# 01_MAIN.net
KiCad netlist of a schematic drawn in Altium Designer
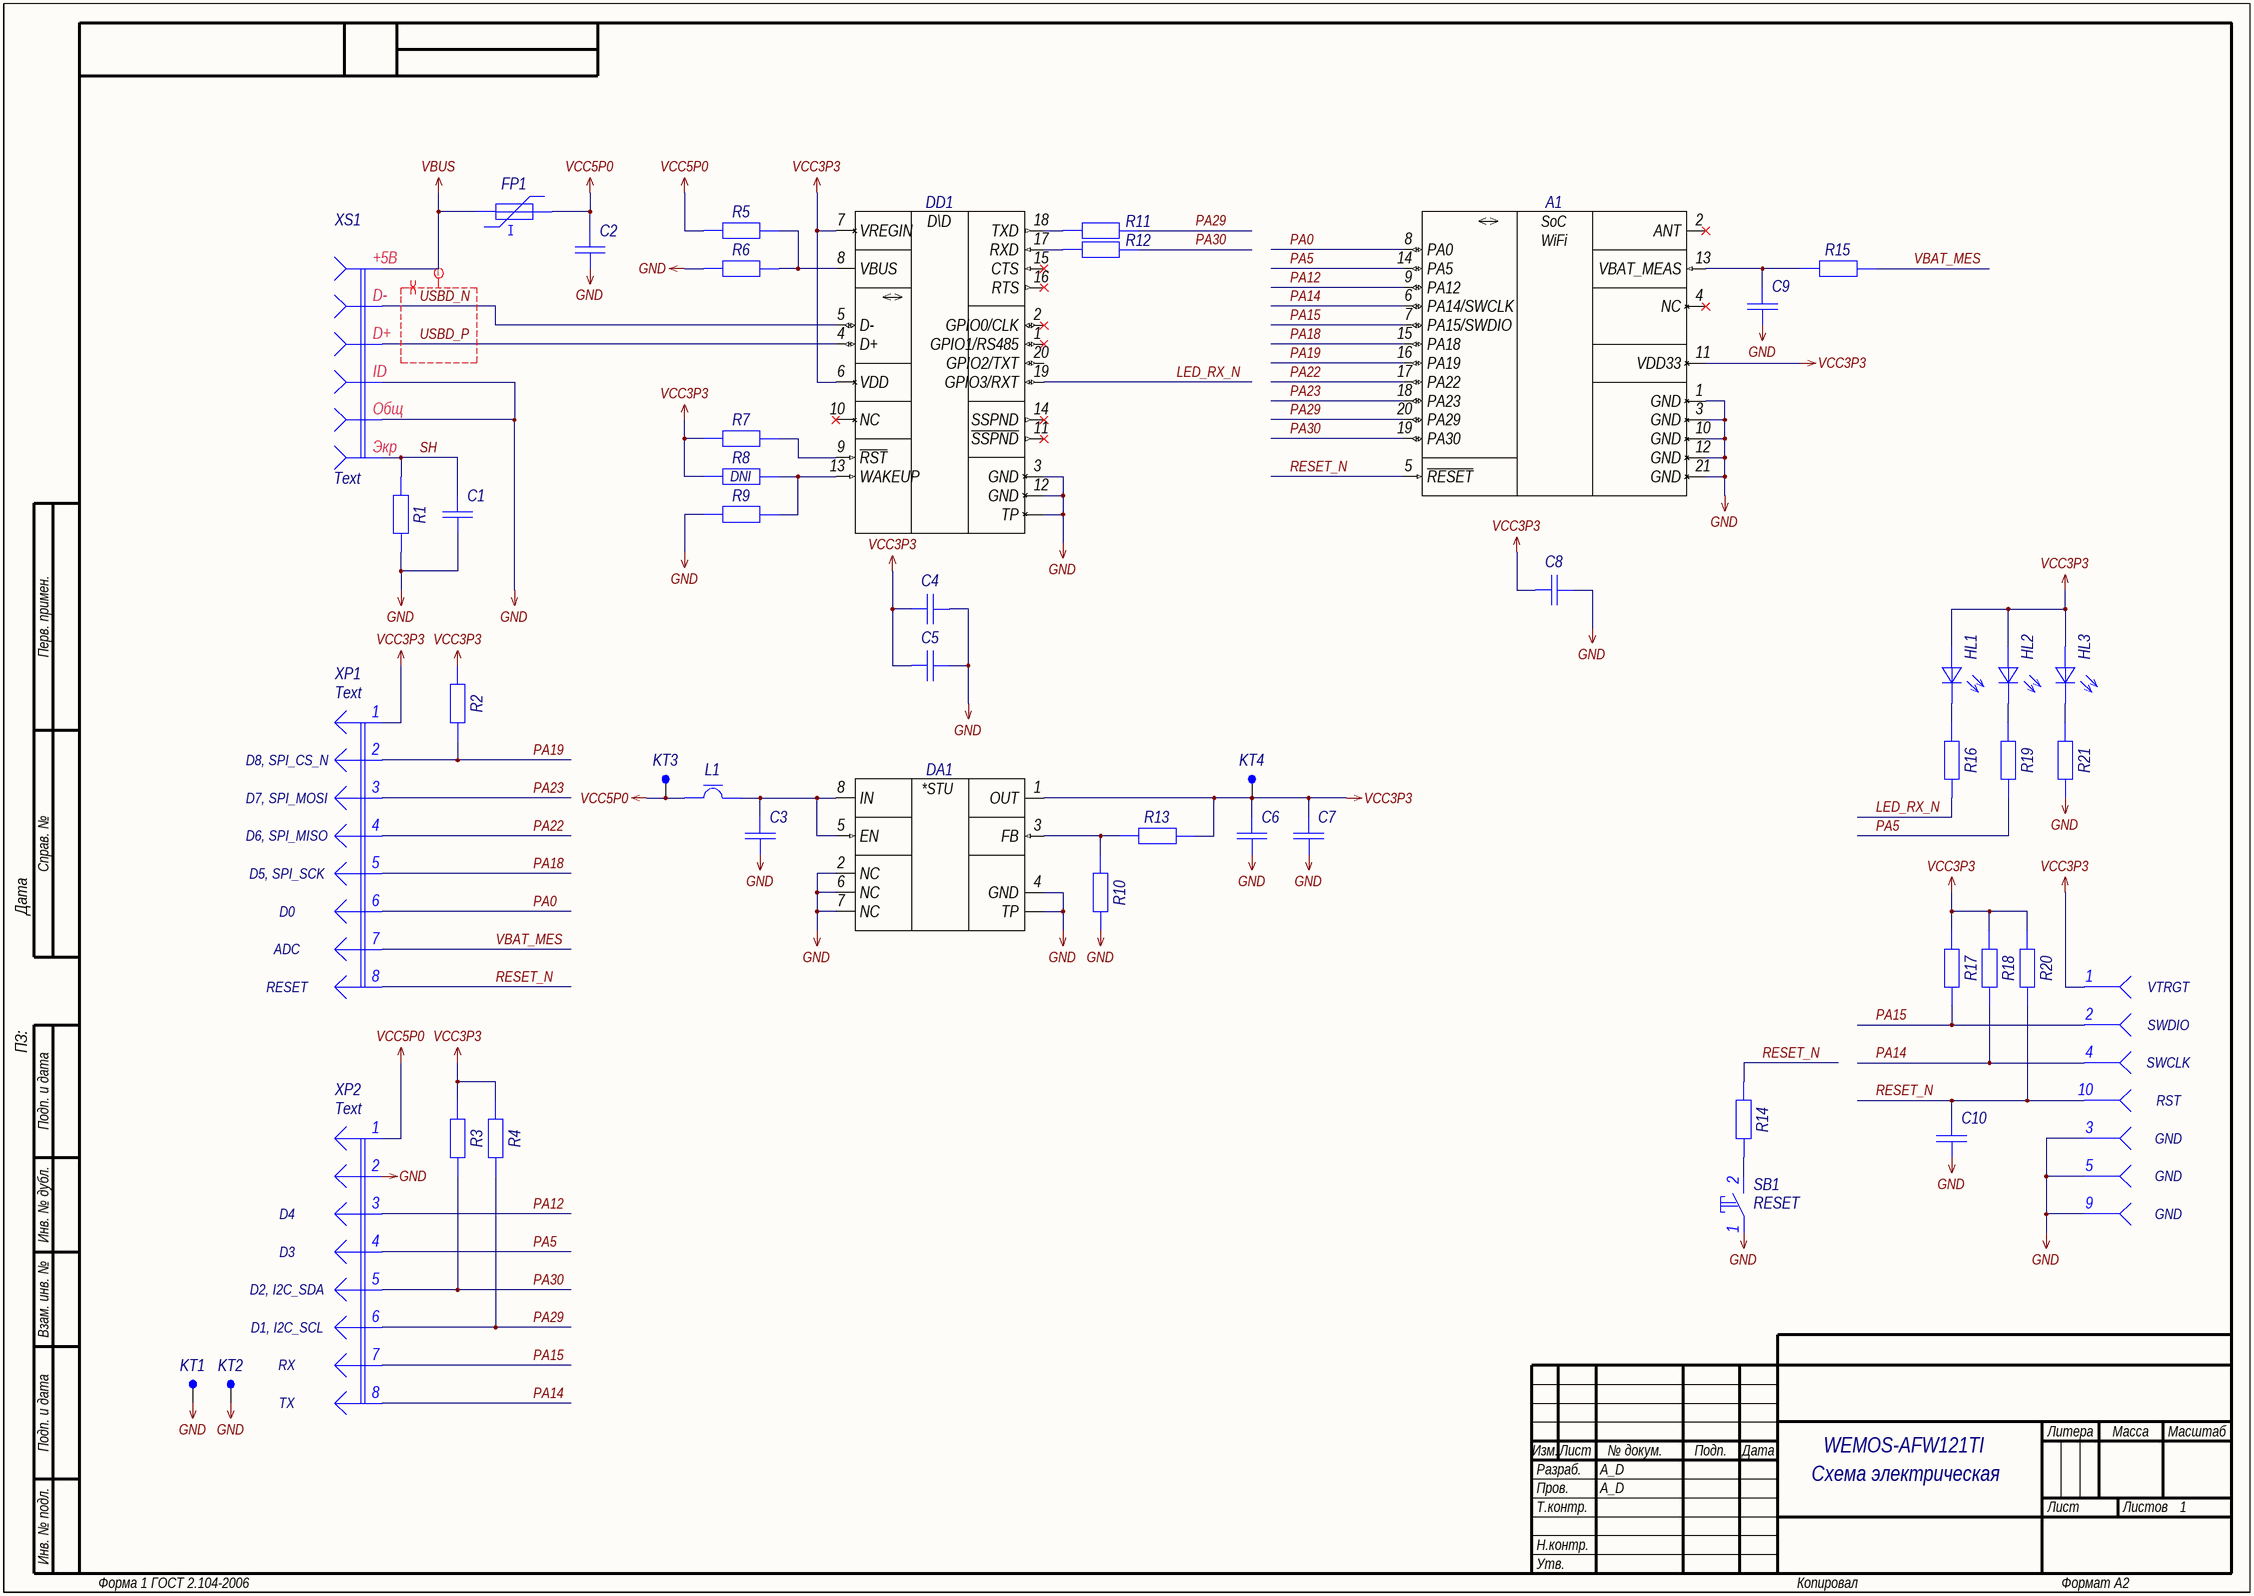
[diagram p0: 01_MAIN.SchDoc]

(export (version "E")
  (design (tool "Eeschema 10.0.6"))
  (components
    (comp (ref "A1")
      (value "AFW121TI")
      (footprint "AFW121TI")
      (fields (field (name "MANUFACTURER") "99IOT") (field (name "PUBLISHER") "Andrew Danich"))
      (libsource (lib "ADLib") (part "AFW121TI"))
    )
    (comp (ref "C1")
      (value "Capacitor")
      (footprint "C0603_L")
      (fields
        (field (name "PART NUMBER") "GRM188R72A104KA35D")
        (field (name "VOLTAGE") "100V")
        (field (name "TOLERANCE") "±10%")
        (field (name "PUBLISHER") "Andrew Danich")
      )
      (libsource (lib "ADLib") (part "Capacitor"))
    )
    (comp (ref "C2")
      (value "Capacitor")
      (footprint "C0603_L")
      (fields
        (field (name "PART NUMBER") "GRM188R60J106ME47D")
        (field (name "VOLTAGE") "6.3V")
        (field (name "TOLERANCE") "±20%")
        (field (name "PUBLISHER") "Andrew Danich")
      )
      (libsource (lib "ADLib") (part "Capacitor"))
    )
    (comp (ref "C3")
      (value "Capacitor")
      (footprint "C0402_L")
      (fields
        (field (name "PART NUMBER") "GRM155R60J475ME87D")
        (field (name "VOLTAGE") "6.3V")
        (field (name "TOLERANCE") "±20%")
        (field (name "PUBLISHER") "Andrew Danich")
      )
      (libsource (lib "ADLib") (part "Capacitor"))
    )
    (comp (ref "C4")
      (value "Capacitor")
      (footprint "C0402_L")
      (fields
        (field (name "PART NUMBER") "GRM155R60J475ME87D")
        (field (name "VOLTAGE") "6.3V")
        (field (name "TOLERANCE") "±20%")
        (field (name "PUBLISHER") "Andrew Danich")
      )
      (libsource (lib "ADLib") (part "Capacitor"))
    )
    (comp (ref "C5")
      (value "Capacitor")
      (footprint "C0402_L")
      (fields
        (field (name "PART NUMBER") "GCM155R71C104KA55D")
        (field (name "VOLTAGE") "16V")
        (field (name "TOLERANCE") "±10%")
        (field (name "PUBLISHER") "Andrew Danich")
      )
      (libsource (lib "ADLib") (part "Capacitor"))
    )
    (comp (ref "C6")
      (value "Capacitor")
      (footprint "C0402_L")
      (fields
        (field (name "PART NUMBER") "GRM155R60J475ME87D")
        (field (name "VOLTAGE") "6.3V")
        (field (name "TOLERANCE") "±20%")
        (field (name "PUBLISHER") "Andrew Danich")
      )
      (libsource (lib "ADLib") (part "Capacitor"))
    )
    (comp (ref "C7")
      (value "Capacitor")
      (footprint "C0402_L")
      (fields
        (field (name "PART NUMBER") "GRM155R60J475ME87D")
        (field (name "VOLTAGE") "6.3V")
        (field (name "TOLERANCE") "±20%")
        (field (name "PUBLISHER") "Andrew Danich")
      )
      (libsource (lib "ADLib") (part "Capacitor"))
    )
    (comp (ref "C8")
      (value "Capacitor")
      (footprint "C0402_L")
      (fields
        (field (name "PART NUMBER") "GRM155R60J475ME87D")
        (field (name "VOLTAGE") "6.3V")
        (field (name "TOLERANCE") "±20%")
        (field (name "PUBLISHER") "Andrew Danich")
      )
      (libsource (lib "ADLib") (part "Capacitor"))
    )
    (comp (ref "C9")
      (value "Capacitor")
      (footprint "C0402_L")
      (fields
        (field (name "PART NUMBER") "GCM1555C1H101FA16D")
        (field (name "VOLTAGE") "50V")
        (field (name "TOLERANCE") "±1%")
        (field (name "PUBLISHER") "Andrew Danich")
      )
      (libsource (lib "ADLib") (part "Capacitor"))
    )
    (comp (ref "C10")
      (value "Capacitor")
      (footprint "C0402_L")
      (fields
        (field (name "PART NUMBER") "GCM155R71C104KA55D")
        (field (name "VOLTAGE") "16V")
        (field (name "TOLERANCE") "±10%")
        (field (name "PUBLISHER") "Andrew Danich")
      )
      (libsource (lib "ADLib") (part "Capacitor"))
    )
    (comp (ref "DA1")
      (value "TPS73701DRB")
      (footprint "VSON-8_065P300X300X100_N")
      (fields
        (field (name "PART NUMBER") "TPS73701DRBR")
        (field (name "MANUFACTURER") "Texas Instruments")
        (field (name "PUBLISHER") "Andrew Danich")
      )
      (libsource (lib "ADLib") (part "TPS73701DRB"))
    )
    (comp (ref "DD1")
      (value "CP2102N-xxx-GQFN20")
      (footprint "QFN-20_050P300X300X080_N")
      (fields
        (field (name "PART NUMBER") "CP2102N-A01-GQFN20")
        (field (name "MANUFACTURER") "Silicon Labs")
        (field (name "PUBLISHER") "Andrew Danich")
      )
      (libsource (lib "ADLib") (part "CP2102N-xxx-GQFN20"))
    )
    (comp (ref "FP1")
      (value "Fuse_PTC")
      (footprint "F0603_L_H075")
      (fields (field (name "PART NUMBER") "0603L100SLYR") (field (name "MANUFACTURER") "Littelfuse"))
      (libsource (lib "ADLib") (part "Fuse_PTC"))
    )
    (comp (ref "HL1")
      (value "RX")
      (footprint "LD0402_L")
      (fields
        (field (name "PART NUMBER") "KPHHS-1005SURCK")
        (field (name "MANUFACTURER") "Kingbright")
        (field (name "PUBLISHER") "Andrew Danich")
      )
      (libsource (lib "ADLib") (part "Led-1"))
    )
    (comp (ref "HL2")
      (value "USER")
      (footprint "LD0402_L")
      (fields
        (field (name "PART NUMBER") "KPHHS-1005QBC-D-V")
        (field (name "MANUFACTURER") "Kingbright")
        (field (name "PUBLISHER") "Andrew Danich")
      )
      (libsource (lib "ADLib") (part "Led-1"))
    )
    (comp (ref "HL3")
      (value "POWER")
      (footprint "LD0402_L")
      (fields
        (field (name "PART NUMBER") "KPHHS-1005CGCK")
        (field (name "MANUFACTURER") "Kingbright")
        (field (name "PUBLISHER") "Andrew Danich")
      )
      (libsource (lib "ADLib") (part "Led-1"))
    )
    (comp (ref "KT1")
      (value "GND")
      (footprint "TP-SMT-R-0.8mm")
      (fields (field (name "PART NUMBER") "TestPoint-SMT-GND") (field (name "PUBLISHER") "Andrew Danich"))
      (libsource (lib "ADLib") (part "TP-S-1"))
    )
    (comp (ref "KT2")
      (value "GND")
      (footprint "TP-SMT-R-0.8mm")
      (fields (field (name "PART NUMBER") "TestPoint-SMT-GND") (field (name "PUBLISHER") "Andrew Danich"))
      (libsource (lib "ADLib") (part "TP-S-1"))
    )
    (comp (ref "KT3")
      (value "+5P0")
      (footprint "TP-SMT-C-0.5mm")
      (fields (field (name "PART NUMBER") "TestPoint-SMT") (field (name "PUBLISHER") "Andrew Danich"))
      (libsource (lib "ADLib") (part "TP-S-1"))
    )
    (comp (ref "KT4")
      (value "+3P3")
      (footprint "TP-SMT-C-0.5mm")
      (fields (field (name "PART NUMBER") "TestPoint-SMT") (field (name "PUBLISHER") "Andrew Danich"))
      (libsource (lib "ADLib") (part "TP-S-1"))
    )
    (comp (ref "L1")
      (value "FerriteBead")
      (footprint "L0402_L")
      (fields
        (field (name "PART NUMBER") "BLM15PD121SN1D")
        (field (name "TOLERANCE") "±25%")
        (field (name "MANUFACTURER") "Murata")
        (field (name "PUBLISHER") "Andrew Danich")
      )
      (libsource (lib "ADLib") (part "FerriteBead"))
    )
    (comp (ref "R1")
      (value "Resistor")
      (footprint "R0603_L")
      (fields
        (field (name "PART NUMBER") "RC0603JR-070R")
        (field (name "TOLERANCE") "±5%")
        (field (name "MANUFACTURER") "Yageo")
        (field (name "PUBLISHER") "Andrew Danich")
      )
      (libsource (lib "ADLib") (part "Resistor"))
    )
    (comp (ref "R2")
      (value "Resistor")
      (footprint "R0402_L")
      (fields
        (field (name "PART NUMBER") "RC0402JR-0710KL")
        (field (name "TOLERANCE") "±5%")
        (field (name "MANUFACTURER") "Yageo")
        (field (name "PUBLISHER") "Andrew Danich")
      )
      (libsource (lib "ADLib") (part "Resistor"))
    )
    (comp (ref "R3")
      (value "Resistor")
      (footprint "R0402_L")
      (fields
        (field (name "PART NUMBER") "RC0402JR-0710KL")
        (field (name "TOLERANCE") "±5%")
        (field (name "MANUFACTURER") "Yageo")
        (field (name "PUBLISHER") "Andrew Danich")
      )
      (libsource (lib "ADLib") (part "Resistor"))
    )
    (comp (ref "R4")
      (value "Resistor")
      (footprint "R0402_L")
      (fields
        (field (name "PART NUMBER") "RC0402JR-0710KL")
        (field (name "TOLERANCE") "±5%")
        (field (name "MANUFACTURER") "Yageo")
        (field (name "PUBLISHER") "Andrew Danich")
      )
      (libsource (lib "ADLib") (part "Resistor"))
    )
    (comp (ref "R5")
      (value "Resistor")
      (footprint "R0402_L")
      (fields
        (field (name "PART NUMBER") "RC0402FR-0722K1L")
        (field (name "TOLERANCE") "±1%")
        (field (name "MANUFACTURER") "Yageo")
        (field (name "PUBLISHER") "Andrew Danich")
      )
      (libsource (lib "ADLib") (part "Resistor"))
    )
    (comp (ref "R6")
      (value "Resistor")
      (footprint "R0402_L")
      (fields
        (field (name "PART NUMBER") "RC0402FR-0747KL")
        (field (name "TOLERANCE") "±1%")
        (field (name "MANUFACTURER") "Yageo")
        (field (name "PUBLISHER") "Andrew Danich")
      )
      (libsource (lib "ADLib") (part "Resistor"))
    )
    (comp (ref "R7")
      (value "Resistor")
      (footprint "R0402_L")
      (fields
        (field (name "PART NUMBER") "RC0402JR-0710KL")
        (field (name "TOLERANCE") "±5%")
        (field (name "MANUFACTURER") "Yageo")
        (field (name "PUBLISHER") "Andrew Danich")
      )
      (libsource (lib "ADLib") (part "Resistor"))
    )
    (comp (ref "R8")
      (value "Resistor")
      (footprint "R0402_L")
      (fields
        (field (name "PART NUMBER") "RC0402JR-0710KL")
        (field (name "TOLERANCE") "±5%")
        (field (name "MANUFACTURER") "Yageo")
        (field (name "PUBLISHER") "Andrew Danich")
      )
      (libsource (lib "ADLib") (part "Resistor"))
    )
    (comp (ref "R9")
      (value "Resistor")
      (footprint "R0402_L")
      (fields
        (field (name "PART NUMBER") "RC0402JR-070RL")
        (field (name "TOLERANCE") "±5%")
        (field (name "MANUFACTURER") "Yageo")
        (field (name "PUBLISHER") "Andrew Danich")
      )
      (libsource (lib "ADLib") (part "Resistor"))
    )
    (comp (ref "R10")
      (value "Resistor")
      (footprint "R0402_L")
      (fields
        (field (name "PART NUMBER") "RC0402FR-0712KL")
        (field (name "TOLERANCE") "±1%")
        (field (name "MANUFACTURER") "Yageo")
        (field (name "PUBLISHER") "Andrew Danich")
      )
      (libsource (lib "ADLib") (part "Resistor"))
    )
    (comp (ref "R11")
      (value "Resistor")
      (footprint "R0402_L")
      (fields
        (field (name "PART NUMBER") "RC0402JR-070RL")
        (field (name "TOLERANCE") "±5%")
        (field (name "MANUFACTURER") "Yageo")
        (field (name "PUBLISHER") "Andrew Danich")
      )
      (libsource (lib "ADLib") (part "Resistor"))
    )
    (comp (ref "R12")
      (value "Resistor")
      (footprint "R0402_L")
      (fields
        (field (name "PART NUMBER") "RC0402JR-070RL")
        (field (name "TOLERANCE") "±5%")
        (field (name "MANUFACTURER") "Yageo")
        (field (name "PUBLISHER") "Andrew Danich")
      )
      (libsource (lib "ADLib") (part "Resistor"))
    )
    (comp (ref "R13")
      (value "Resistor")
      (footprint "R0402_L")
      (fields
        (field (name "PART NUMBER") "RC0402FR-0722K1L")
        (field (name "TOLERANCE") "±1%")
        (field (name "MANUFACTURER") "Yageo")
        (field (name "PUBLISHER") "Andrew Danich")
      )
      (libsource (lib "ADLib") (part "Resistor"))
    )
    (comp (ref "R14")
      (value "Resistor")
      (footprint "R0402_L")
      (fields
        (field (name "PART NUMBER") "RC0402JR-0720RL")
        (field (name "TOLERANCE") "±5%")
        (field (name "MANUFACTURER") "Yageo")
        (field (name "PUBLISHER") "Andrew Danich")
      )
      (libsource (lib "ADLib") (part "Resistor"))
    )
    (comp (ref "R15")
      (value "Resistor")
      (footprint "R0402_L")
      (fields
        (field (name "PART NUMBER") "RC0402JR-07100RL")
        (field (name "TOLERANCE") "±5%")
        (field (name "MANUFACTURER") "Yageo")
        (field (name "PUBLISHER") "Andrew Danich")
      )
      (libsource (lib "ADLib") (part "Resistor"))
    )
    (comp (ref "R16")
      (value "Resistor")
      (footprint "R0402_L")
      (fields
        (field (name "PART NUMBER") "RC0402JR-071KL")
        (field (name "TOLERANCE") "±5%")
        (field (name "MANUFACTURER") "Yageo")
        (field (name "PUBLISHER") "Andrew Danich")
      )
      (libsource (lib "ADLib") (part "Resistor"))
    )
    (comp (ref "R17")
      (value "Resistor")
      (footprint "R0402_L")
      (fields
        (field (name "PART NUMBER") "RC0402JR-0710KL")
        (field (name "TOLERANCE") "±5%")
        (field (name "MANUFACTURER") "Yageo")
        (field (name "PUBLISHER") "Andrew Danich")
      )
      (libsource (lib "ADLib") (part "Resistor"))
    )
    (comp (ref "R18")
      (value "Resistor")
      (footprint "R0402_L")
      (fields
        (field (name "PART NUMBER") "RC0402JR-0710KL")
        (field (name "TOLERANCE") "±5%")
        (field (name "MANUFACTURER") "Yageo")
        (field (name "PUBLISHER") "Andrew Danich")
      )
      (libsource (lib "ADLib") (part "Resistor"))
    )
    (comp (ref "R19")
      (value "Resistor")
      (footprint "R0402_L")
      (fields
        (field (name "PART NUMBER") "RC0402JR-071KL")
        (field (name "TOLERANCE") "±5%")
        (field (name "MANUFACTURER") "Yageo")
        (field (name "PUBLISHER") "Andrew Danich")
      )
      (libsource (lib "ADLib") (part "Resistor"))
    )
    (comp (ref "R20")
      (value "Resistor")
      (footprint "R0402_L")
      (fields
        (field (name "PART NUMBER") "RC0402JR-0710KL")
        (field (name "TOLERANCE") "±5%")
        (field (name "MANUFACTURER") "Yageo")
        (field (name "PUBLISHER") "Andrew Danich")
      )
      (libsource (lib "ADLib") (part "Resistor"))
    )
    (comp (ref "R21")
      (value "Resistor")
      (footprint "R0402_L")
      (fields
        (field (name "PART NUMBER") "RC0402JR-071KL")
        (field (name "TOLERANCE") "±5%")
        (field (name "MANUFACTURER") "Yageo")
        (field (name "PUBLISHER") "Andrew Danich")
      )
      (libsource (lib "ADLib") (part "Resistor"))
    )
    (comp (ref "SB1")
      (value "RESET")
      (footprint "1TS003B-Series")
      (fields
        (field (name "PART NUMBER") "1TS003B-1600-3500A-CT")
        (field (name "MANUFACTURER") "Hongyuan Precision")
        (field (name "PUBLISHER") "Andrew Danich")
      )
      (libsource (lib "ADLib") (part "BT-01x-01p"))
    )
    (comp (ref "XP1")
      (value "Text")
      (footprint "PLS-8")
      (fields (field (name "PART NUMBER") "PLS-8") (field (name "PUBLISHER") "Andrew Danich"))
      (libsource (lib "ADLib") (part "Con-8-M"))
    )
    (comp (ref "XP2")
      (value "Text")
      (footprint "PLS-8")
      (fields (field (name "PART NUMBER") "PLS-8") (field (name "PUBLISHER") "Andrew Danich"))
      (libsource (lib "ADLib") (part "Con-8-M"))
    )
    (comp (ref "XS1")
      (value "Text")
      (footprint "1981568-1")
      (fields
        (field (name "PART NUMBER") "1981568-1")
        (field (name "MANUFACTURER") "TE Connectivity")
        (field (name "PUBLISHER") "Andrew Danich")
      )
      (libsource (lib "ADLib") (part "Con-6-F-USB"))
    )
    (comp (ref "XS2")
      (value "JTAG")
      (footprint "XF2M-1015-1A")
      (fields
        (field (name "PART NUMBER") "XF2M-1015-1A")
        (field (name "MANUFACTURER") "Omron Electronics")
        (field (name "PUBLISHER") "Viktor Klishin")
      )
      (libsource (lib "ADLib") (part "Con-10-F_S"))
    )
  )
  (nets
    (net (code "1") (name "/LED_RX_N") (class "Default")
      (node (ref "DD1") (pin "19") (pinfunction "GPIO3/RXT_19") (pintype "bidirectional"))
      (node (ref "R16") (pin "1") (pinfunction "1_1") (pintype "passive"))
    )
    (net (code "2") (name "/PA0") (class "Default")
      (node (ref "A1") (pin "8") (pinfunction "PA0_8") (pintype "bidirectional"))
      (node (ref "XP1") (pin "6") (pintype "passive"))
    )
    (net (code "3") (name "/PA5") (class "Default")
      (node (ref "A1") (pin "14") (pinfunction "PA5_14") (pintype "bidirectional"))
      (node (ref "R19") (pin "1") (pinfunction "1_1") (pintype "passive"))
      (node (ref "XP2") (pin "4") (pintype "passive"))
    )
    (net (code "4") (name "/PA12") (class "Default")
      (node (ref "A1") (pin "9") (pinfunction "PA12_9") (pintype "bidirectional"))
      (node (ref "XP2") (pin "3") (pintype "passive"))
    )
    (net (code "5") (name "/PA14") (class "Default")
      (node (ref "A1") (pin "6") (pinfunction "PA14/SWCLK_6") (pintype "bidirectional"))
      (node (ref "R18") (pin "2") (pinfunction "2_2") (pintype "passive"))
      (node (ref "XP2") (pin "8") (pintype "passive"))
      (node (ref "XS2") (pin "4") (pintype "passive"))
    )
    (net (code "6") (name "/PA15") (class "Default")
      (node (ref "A1") (pin "7") (pinfunction "PA15/SWDIO_7") (pintype "bidirectional"))
      (node (ref "R17") (pin "2") (pinfunction "2_2") (pintype "passive"))
      (node (ref "XP2") (pin "7") (pintype "passive"))
      (node (ref "XS2") (pin "2") (pintype "passive"))
    )
    (net (code "7") (name "/PA18") (class "Default")
      (node (ref "A1") (pin "15") (pinfunction "PA18_15") (pintype "bidirectional"))
      (node (ref "XP1") (pin "5") (pintype "passive"))
    )
    (net (code "8") (name "/PA19") (class "Default")
      (node (ref "A1") (pin "16") (pinfunction "PA19_16") (pintype "bidirectional"))
      (node (ref "R2") (pin "2") (pinfunction "2_2") (pintype "passive"))
      (node (ref "XP1") (pin "2") (pintype "passive"))
    )
    (net (code "9") (name "/PA22") (class "Default")
      (node (ref "A1") (pin "17") (pinfunction "PA22_17") (pintype "bidirectional"))
      (node (ref "XP1") (pin "4") (pintype "passive"))
    )
    (net (code "10") (name "/PA23") (class "Default")
      (node (ref "A1") (pin "18") (pinfunction "PA23_18") (pintype "bidirectional"))
      (node (ref "XP1") (pin "3") (pintype "passive"))
    )
    (net (code "11") (name "/PA29") (class "Default")
      (node (ref "A1") (pin "20") (pinfunction "PA29_20") (pintype "bidirectional"))
      (node (ref "R11") (pin "2") (pinfunction "2_2") (pintype "passive"))
      (node (ref "R4") (pin "2") (pinfunction "2_2") (pintype "passive"))
      (node (ref "XP2") (pin "6") (pintype "passive"))
    )
    (net (code "12") (name "/PA30") (class "Default")
      (node (ref "A1") (pin "19") (pinfunction "PA30_19") (pintype "bidirectional"))
      (node (ref "R12") (pin "2") (pinfunction "2_2") (pintype "passive"))
      (node (ref "R3") (pin "2") (pinfunction "2_2") (pintype "passive"))
      (node (ref "XP2") (pin "5") (pintype "passive"))
    )
    (net (code "13") (name "/RESET_N") (class "Default")
      (node (ref "A1") (pin "5") (pinfunction "~{RESET}_5") (pintype "input"))
      (node (ref "C10") (pin "2") (pinfunction "2_2") (pintype "passive"))
      (node (ref "R14") (pin "2") (pinfunction "2_2") (pintype "passive"))
      (node (ref "R20") (pin "2") (pinfunction "2_2") (pintype "passive"))
      (node (ref "XP1") (pin "8") (pintype "passive"))
      (node (ref "XS2") (pin "10") (pintype "passive"))
    )
    (net (code "14") (name "/SH") (class "Default")
      (node (ref "C1") (pin "2") (pinfunction "2_2") (pintype "passive"))
      (node (ref "R1") (pin "2") (pinfunction "2_2") (pintype "passive"))
      (node (ref "XS1") (pin "6") (pintype "passive"))
    )
    (net (code "15") (name "/USBD_N") (class "Default")
      (node (ref "DD1") (pin "5") (pinfunction "D-_5") (pintype "bidirectional"))
      (node (ref "XS1") (pin "2") (pintype "passive"))
    )
    (net (code "16") (name "/USBD_P") (class "Default")
      (node (ref "DD1") (pin "4") (pinfunction "D+_4") (pintype "bidirectional"))
      (node (ref "XS1") (pin "3") (pintype "passive"))
    )
    (net (code "17") (name "/VBAT_MES") (class "Default")
      (node (ref "R15") (pin "2") (pinfunction "2_2") (pintype "passive"))
      (node (ref "XP1") (pin "7") (pintype "passive"))
    )
    (net (code "18") (name "GND") (class "Default")
      (node (ref "A1") (pin "1") (pinfunction "GND_1") (pintype "power_in"))
      (node (ref "A1") (pin "10") (pinfunction "GND_10") (pintype "power_in"))
      (node (ref "A1") (pin "12") (pinfunction "GND_12") (pintype "power_in"))
      (node (ref "A1") (pin "21") (pinfunction "GND_21") (pintype "power_in"))
      (node (ref "A1") (pin "3") (pinfunction "GND_3") (pintype "power_in"))
      (node (ref "C1") (pin "1") (pinfunction "1_1") (pintype "passive"))
      (node (ref "C10") (pin "1") (pinfunction "1_1") (pintype "passive"))
      (node (ref "C2") (pin "1") (pinfunction "1_1") (pintype "passive"))
      (node (ref "C3") (pin "1") (pinfunction "1_1") (pintype "passive"))
      (node (ref "C4") (pin "1") (pinfunction "1_1") (pintype "passive"))
      (node (ref "C5") (pin "1") (pinfunction "1_1") (pintype "passive"))
      (node (ref "C6") (pin "1") (pinfunction "1_1") (pintype "passive"))
      (node (ref "C7") (pin "1") (pinfunction "1_1") (pintype "passive"))
      (node (ref "C8") (pin "1") (pinfunction "1_1") (pintype "passive"))
      (node (ref "C9") (pin "1") (pinfunction "1_1") (pintype "passive"))
      (node (ref "DA1") (pin "2") (pinfunction "NC_2") (pintype "passive"))
      (node (ref "DA1") (pin "4") (pinfunction "GND_4") (pintype "power_in"))
      (node (ref "DA1") (pin "6") (pinfunction "NC_6") (pintype "passive"))
      (node (ref "DA1") (pin "7") (pinfunction "NC_7") (pintype "passive"))
      (node (ref "DA1") (pin "TP") (pinfunction "TP_TP") (pintype "passive"))
      (node (ref "DD1") (pin "12") (pinfunction "GND_12") (pintype "power_in"))
      (node (ref "DD1") (pin "3") (pinfunction "GND_3") (pintype "power_in"))
      (node (ref "DD1") (pin "TP") (pinfunction "TP_TP") (pintype "power_in"))
      (node (ref "KT1") (pin "1") (pinfunction "1_1") (pintype "passive"))
      (node (ref "KT2") (pin "1") (pinfunction "1_1") (pintype "passive"))
      (node (ref "R1") (pin "1") (pinfunction "1_1") (pintype "passive"))
      (node (ref "R10") (pin "1") (pinfunction "1_1") (pintype "passive"))
      (node (ref "R21") (pin "1") (pinfunction "1_1") (pintype "passive"))
      (node (ref "R6") (pin "1") (pinfunction "1_1") (pintype "passive"))
      (node (ref "R9") (pin "1") (pinfunction "1_1") (pintype "passive"))
      (node (ref "SB1") (pin "1") (pintype "passive"))
      (node (ref "XP2") (pin "2") (pintype "passive"))
      (node (ref "XS1") (pin "4") (pintype "passive"))
      (node (ref "XS1") (pin "5") (pintype "passive"))
      (node (ref "XS2") (pin "3") (pintype "passive"))
      (node (ref "XS2") (pin "5") (pintype "passive"))
      (node (ref "XS2") (pin "9") (pintype "passive"))
    )
    (net (code "19") (name "Net-(A1-VBAT_MEAS)") (class "Default")
      (node (ref "A1") (pin "13") (pinfunction "VBAT_MEAS_13") (pintype "input"))
      (node (ref "C9") (pin "2") (pinfunction "2_2") (pintype "passive"))
      (node (ref "R15") (pin "1") (pinfunction "1_1") (pintype "passive"))
    )
    (net (code "20") (name "Net-(DA1-EN)") (class "Default")
      (node (ref "C3") (pin "2") (pinfunction "2_2") (pintype "passive"))
      (node (ref "DA1") (pin "5") (pinfunction "EN_5") (pintype "input"))
      (node (ref "DA1") (pin "8") (pinfunction "IN_8") (pintype "power_in"))
      (node (ref "L1") (pin "2") (pinfunction "2_2") (pintype "passive"))
    )
    (net (code "21") (name "Net-(DA1-FB)") (class "Default")
      (node (ref "DA1") (pin "3") (pinfunction "FB_3") (pintype "input"))
      (node (ref "R10") (pin "2") (pinfunction "2_2") (pintype "passive"))
      (node (ref "R13") (pin "1") (pinfunction "1_1") (pintype "passive"))
    )
    (net (code "22") (name "Net-(DD1-RXD)") (class "Default")
      (node (ref "DD1") (pin "17") (pinfunction "RXD_17") (pintype "input"))
      (node (ref "R12") (pin "1") (pinfunction "1_1") (pintype "passive"))
    )
    (net (code "23") (name "Net-(DD1-TXD)") (class "Default")
      (node (ref "DD1") (pin "18") (pinfunction "TXD_18") (pintype "output"))
      (node (ref "R11") (pin "1") (pinfunction "1_1") (pintype "passive"))
    )
    (net (code "24") (name "Net-(DD1-VBUS)") (class "Default")
      (node (ref "DD1") (pin "8") (pinfunction "VBUS_8") (pintype "power_in"))
      (node (ref "R5") (pin "2") (pinfunction "2_2") (pintype "passive"))
      (node (ref "R6") (pin "2") (pinfunction "2_2") (pintype "passive"))
    )
    (net (code "25") (name "Net-(DD1-WAKEUP)") (class "Default")
      (node (ref "DD1") (pin "13") (pinfunction "WAKEUP_13") (pintype "input"))
      (node (ref "R8") (pin "1") (pinfunction "1_1") (pintype "passive"))
      (node (ref "R9") (pin "2") (pinfunction "2_2") (pintype "passive"))
    )
    (net (code "26") (name "Net-(DD1-~{RST})") (class "Default")
      (node (ref "DD1") (pin "9") (pinfunction "~{RST}_9") (pintype "input"))
      (node (ref "R7") (pin "1") (pinfunction "1_1") (pintype "passive"))
    )
    (net (code "27") (name "Net-(HL1-К)") (class "Default")
      (node (ref "HL1") (pin "2") (pinfunction "К_2") (pintype "passive"))
      (node (ref "R16") (pin "2") (pinfunction "2_2") (pintype "passive"))
    )
    (net (code "28") (name "Net-(HL2-К)") (class "Default")
      (node (ref "HL2") (pin "2") (pinfunction "К_2") (pintype "passive"))
      (node (ref "R19") (pin "2") (pinfunction "2_2") (pintype "passive"))
    )
    (net (code "29") (name "Net-(HL3-К)") (class "Default")
      (node (ref "HL3") (pin "2") (pinfunction "К_2") (pintype "passive"))
      (node (ref "R21") (pin "2") (pinfunction "2_2") (pintype "passive"))
    )
    (net (code "30") (name "Net-(R14-Pad1)") (class "Default")
      (node (ref "R14") (pin "1") (pinfunction "1_1") (pintype "passive"))
      (node (ref "SB1") (pin "2") (pintype "passive"))
    )
    (net (code "31") (name "VBUS") (class "Default")
      (node (ref "FP1") (pin "1") (pinfunction "1_1") (pintype "passive"))
      (node (ref "XS1") (pin "1") (pintype "passive"))
    )
    (net (code "32") (name "VCC3P3") (class "Default")
      (node (ref "A1") (pin "11") (pinfunction "VDD33_11") (pintype "power_in"))
      (node (ref "C4") (pin "2") (pinfunction "2_2") (pintype "passive"))
      (node (ref "C5") (pin "2") (pinfunction "2_2") (pintype "passive"))
      (node (ref "C6") (pin "2") (pinfunction "2_2") (pintype "passive"))
      (node (ref "C7") (pin "2") (pinfunction "2_2") (pintype "passive"))
      (node (ref "C8") (pin "2") (pinfunction "2_2") (pintype "passive"))
      (node (ref "DA1") (pin "1") (pinfunction "OUT_1") (pintype "power_in"))
      (node (ref "DD1") (pin "6") (pinfunction "VDD_6") (pintype "power_in"))
      (node (ref "DD1") (pin "7") (pinfunction "VREGIN_7") (pintype "power_in"))
      (node (ref "HL1") (pin "1") (pinfunction "А_1") (pintype "passive"))
      (node (ref "HL2") (pin "1") (pinfunction "А_1") (pintype "passive"))
      (node (ref "HL3") (pin "1") (pinfunction "А_1") (pintype "passive"))
      (node (ref "KT4") (pin "1") (pinfunction "1_1") (pintype "passive"))
      (node (ref "R13") (pin "2") (pinfunction "2_2") (pintype "passive"))
      (node (ref "R17") (pin "1") (pinfunction "1_1") (pintype "passive"))
      (node (ref "R18") (pin "1") (pinfunction "1_1") (pintype "passive"))
      (node (ref "R2") (pin "1") (pinfunction "1_1") (pintype "passive"))
      (node (ref "R20") (pin "1") (pinfunction "1_1") (pintype "passive"))
      (node (ref "R3") (pin "1") (pinfunction "1_1") (pintype "passive"))
      (node (ref "R4") (pin "1") (pinfunction "1_1") (pintype "passive"))
      (node (ref "R7") (pin "2") (pinfunction "2_2") (pintype "passive"))
      (node (ref "R8") (pin "2") (pinfunction "2_2") (pintype "passive"))
      (node (ref "XP1") (pin "1") (pintype "passive"))
      (node (ref "XS2") (pin "1") (pintype "passive"))
    )
    (net (code "33") (name "VCC5P0") (class "Default")
      (node (ref "C2") (pin "2") (pinfunction "2_2") (pintype "passive"))
      (node (ref "FP1") (pin "2") (pinfunction "2_2") (pintype "passive"))
      (node (ref "KT3") (pin "1") (pinfunction "1_1") (pintype "passive"))
      (node (ref "L1") (pin "1") (pinfunction "1_1") (pintype "passive"))
      (node (ref "R5") (pin "1") (pinfunction "1_1") (pintype "passive"))
      (node (ref "XP2") (pin "1") (pintype "passive"))
    )
    (net (code "34") (name "unconnected-(A1-ANT-Pad2)") (class "Default")
      (node (ref "A1") (pin "2") (pinfunction "ANT_2") (pintype "passive+no_connect"))
    )
    (net (code "35") (name "unconnected-(A1-NC-Pad4)") (class "Default")
      (node (ref "A1") (pin "4") (pinfunction "NC_4") (pintype "passive+no_connect"))
    )
    (net (code "36") (name "unconnected-(DD1-CTS-Pad15)") (class "Default")
      (node (ref "DD1") (pin "15") (pinfunction "CTS_15") (pintype "input+no_connect"))
    )
    (net (code "37") (name "unconnected-(DD1-GPIO0{slash}CLK-Pad2)") (class "Default")
      (node (ref "DD1") (pin "2") (pinfunction "GPIO0/CLK_2") (pintype "bidirectional+no_connect"))
    )
    (net (code "38") (name "unconnected-(DD1-GPIO1{slash}RS485-Pad1)") (class "Default")
      (node (ref "DD1") (pin "1") (pinfunction "GPIO1/RS485_1") (pintype "bidirectional+no_connect"))
    )
    (net (code "39") (name "unconnected-(DD1-GPIO2{slash}TXT-Pad20)") (class "Default")
      (node (ref "DD1") (pin "20") (pinfunction "GPIO2/TXT_20") (pintype "bidirectional"))
    )
    (net (code "40") (name "unconnected-(DD1-NC-Pad10)") (class "Default")
      (node (ref "DD1") (pin "10") (pinfunction "NC_10") (pintype "passive+no_connect"))
    )
    (net (code "41") (name "unconnected-(DD1-RTS-Pad16)") (class "Default")
      (node (ref "DD1") (pin "16") (pinfunction "RTS_16") (pintype "output+no_connect"))
    )
    (net (code "42") (name "unconnected-(DD1-SSPND-Pad14)") (class "Default")
      (node (ref "DD1") (pin "14") (pinfunction "SSPND_14") (pintype "output+no_connect"))
    )
    (net (code "43") (name "unconnected-(DD1-~{SSPND}-Pad11)") (class "Default")
      (node (ref "DD1") (pin "11") (pinfunction "~{SSPND}_11") (pintype "output+no_connect"))
    )
  )
)
